# schematic.net
KiCad netlist of a schematic drawn in Altium Designer
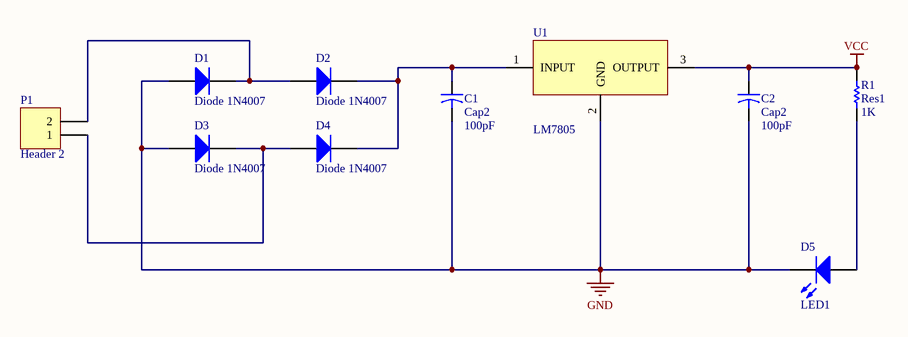
[diagram p0: schematic.SchDoc]

(export (version "E")
  (design (tool "Eeschema 10.0.6"))
  (components
    (comp (ref "C1")
      (value "Cap2")
      (footprint "CAPR5-4X5")
      (description "Capacitor")
      (fields (field (name "ALTIUM_VALUE") "100pF") (field (name "PUBLISHER") "Altium Limited"))
      (libsource (lib "Miscellaneous Devices") (part "Cap2"))
    )
    (comp (ref "C2")
      (value "Cap2")
      (footprint "CAPR5-4X5")
      (description "Capacitor")
      (fields (field (name "ALTIUM_VALUE") "100pF") (field (name "PUBLISHER") "Altium Limited"))
      (libsource (lib "Miscellaneous Devices") (part "Cap2"))
    )
    (comp (ref "D1")
      (value "Diode 1N4007")
      (footprint "DO-41")
      (description "1 Amp General Purpose Rectifier")
      (fields (field (name "PUBLISHER") "Altium Limited"))
      (libsource (lib "Miscellaneous Devices") (part "Diode 1N4007"))
    )
    (comp (ref "D2")
      (value "Diode 1N4007")
      (footprint "DO-41")
      (description "1 Amp General Purpose Rectifier")
      (fields (field (name "PUBLISHER") "Altium Limited"))
      (libsource (lib "Miscellaneous Devices") (part "Diode 1N4007"))
    )
    (comp (ref "D3")
      (value "Diode 1N4007")
      (footprint "DO-41")
      (description "1 Amp General Purpose Rectifier")
      (fields (field (name "PUBLISHER") "Altium Limited"))
      (libsource (lib "Miscellaneous Devices") (part "Diode 1N4007"))
    )
    (comp (ref "D4")
      (value "Diode 1N4007")
      (footprint "DO-41")
      (description "1 Amp General Purpose Rectifier")
      (fields (field (name "PUBLISHER") "Altium Limited"))
      (libsource (lib "Miscellaneous Devices") (part "Diode 1N4007"))
    )
    (comp (ref "D5")
      (value "LED1")
      (footprint "LED-1")
      (description "Typical RED GaAs LED")
      (fields (field (name "PUBLISHER") "Altium Limited"))
      (libsource (lib "Miscellaneous Devices") (part "LED1"))
    )
    (comp (ref "P1")
      (value "Header 2")
      (footprint "HDR1X2")
      (description "Header, 2-Pin")
      (fields (field (name "PUBLISHER") "Altium Limited"))
      (libsource (lib "Miscellaneous Connectors") (part "Header 2"))
    )
    (comp (ref "R1")
      (value "Res1")
      (footprint "AXIAL-0.3")
      (description "Resistor")
      (fields (field (name "ALTIUM_VALUE") "1K") (field (name "PUBLISHER") "Altium Limited"))
      (libsource (lib "Miscellaneous Devices") (part "Res1"))
    )
    (comp (ref "U1") (value "LM7805") (footprint "LM7805") (libsource (lib "LM7805") (part "Component_1")))
  )
  (nets
    (net (code "1") (name "GND") (class "Default")
      (node (ref "C1") (pin "2") (pinfunction "2_2") (pintype "passive"))
      (node (ref "C2") (pin "2") (pinfunction "2_2") (pintype "passive"))
      (node (ref "D1") (pin "1") (pinfunction "A_1") (pintype "passive"))
      (node (ref "D3") (pin "1") (pinfunction "A_1") (pintype "passive"))
      (node (ref "D5") (pin "2") (pinfunction "K_2") (pintype "passive"))
      (node (ref "U1") (pin "2") (pinfunction "GND_2") (pintype "passive"))
    )
    (net (code "2") (name "Net-(D1-K)") (class "Default")
      (node (ref "D1") (pin "2") (pinfunction "K_2") (pintype "passive"))
      (node (ref "D2") (pin "1") (pinfunction "A_1") (pintype "passive"))
      (node (ref "P1") (pin "2") (pinfunction "2_2") (pintype "passive"))
    )
    (net (code "3") (name "Net-(D2-K)") (class "Default")
      (node (ref "C1") (pin "1") (pinfunction "1_1") (pintype "passive"))
      (node (ref "D2") (pin "2") (pinfunction "K_2") (pintype "passive"))
      (node (ref "D4") (pin "2") (pinfunction "K_2") (pintype "passive"))
      (node (ref "U1") (pin "1") (pinfunction "INPUT_1") (pintype "passive"))
    )
    (net (code "4") (name "Net-(D3-K)") (class "Default")
      (node (ref "D3") (pin "2") (pinfunction "K_2") (pintype "passive"))
      (node (ref "D4") (pin "1") (pinfunction "A_1") (pintype "passive"))
      (node (ref "P1") (pin "1") (pinfunction "1_1") (pintype "passive"))
    )
    (net (code "5") (name "Net-(D5-A)") (class "Default")
      (node (ref "D5") (pin "1") (pinfunction "A_1") (pintype "passive"))
      (node (ref "R1") (pin "1") (pinfunction "1_1") (pintype "passive"))
    )
    (net (code "6") (name "VCC") (class "Default")
      (node (ref "C2") (pin "1") (pinfunction "1_1") (pintype "passive"))
      (node (ref "R1") (pin "2") (pinfunction "2_2") (pintype "passive"))
      (node (ref "U1") (pin "3") (pinfunction "OUTPUT_3") (pintype "passive"))
    )
  )
)
